# deserializer.net
KiCad netlist of a schematic drawn in Altium Designer
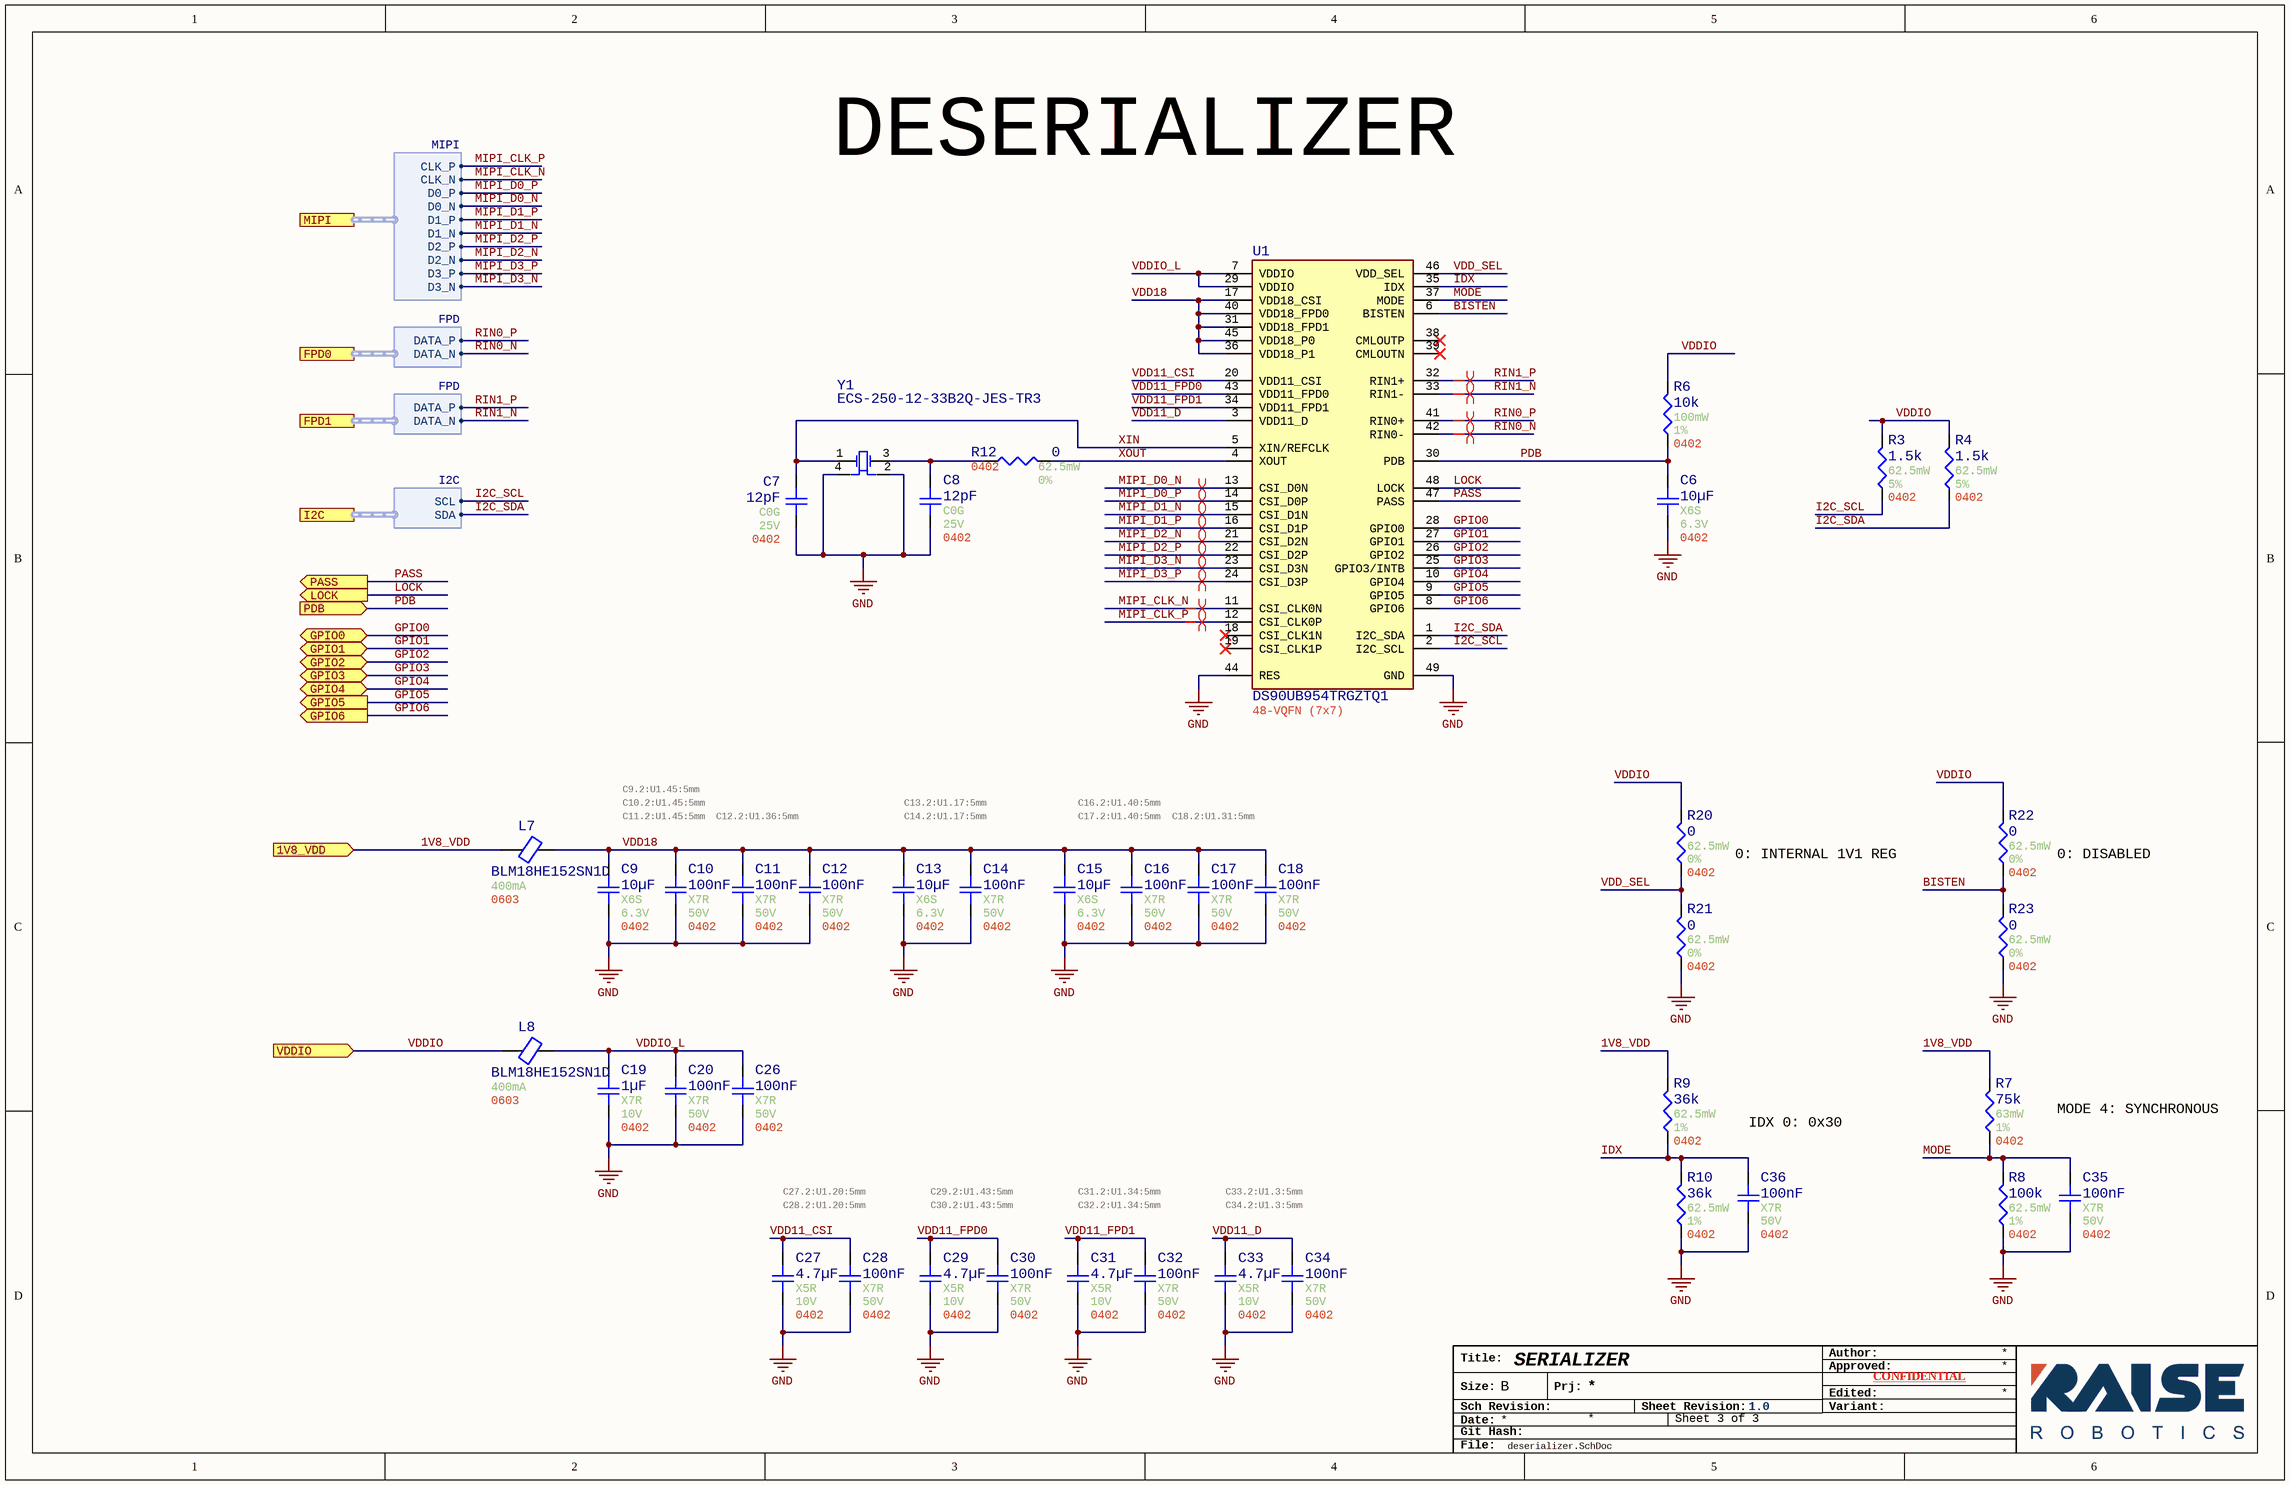
[diagram p0: deserializer.SchDoc]

(export (version "E")
  (design (tool "Eeschema 10.0.6"))
  (components
    (comp (ref "C6")
      (value "10µF")
      (footprint "Generic 0402 capacitor")
      (description "Multilayer Ceramic Capacitors MLCC - SMD/SMT 0402 10uF 6.3VDC 20% X6S AEC-Q200")
      (fields
        (field (name "TEMPERATURE COEFFICIENT") "X6S")
        (field (name "VOLTAGE RATING") "6.3V")
        (field (name "CASE/PACKAGE") "0402")
        (field (name "TOLERANCE") "20%")
        (field (name "Comment") "GRT155C80J106ME13J")
      )
      (libsource (lib "Raise Robotics") (part "Unpolarized Capacitor"))
    )
    (comp (ref "C7")
      (value "12pF")
      (footprint "Generic 0402 capacitor")
      (fields
        (field (name "TEMPERATURE COEFFICIENT") "C0G")
        (field (name "VOLTAGE RATING") "25V")
        (field (name "CASE/PACKAGE") "0402")
        (field (name "TOLERANCE") "5%")
        (field (name "Comment") "GRT1555C1E120JA02J")
      )
      (libsource (lib "Raise Robotics") (part "Unpolarized Capacitor"))
    )
    (comp (ref "C8")
      (value "12pF")
      (footprint "Generic 0402 capacitor")
      (fields
        (field (name "TEMPERATURE COEFFICIENT") "C0G")
        (field (name "VOLTAGE RATING") "25V")
        (field (name "CASE/PACKAGE") "0402")
        (field (name "TOLERANCE") "5%")
        (field (name "Comment") "GRT1555C1E120JA02J")
      )
      (libsource (lib "Raise Robotics") (part "Unpolarized Capacitor"))
    )
    (comp (ref "C9")
      (value "10µF")
      (footprint "Generic 0402 capacitor")
      (description "Multilayer Ceramic Capacitors MLCC - SMD/SMT 0402 10uF 6.3VDC 20% X6S AEC-Q200")
      (fields
        (field (name "TEMPERATURE COEFFICIENT") "X6S")
        (field (name "VOLTAGE RATING") "6.3V")
        (field (name "CASE/PACKAGE") "0402")
        (field (name "TOLERANCE") "20%")
        (field (name "PLACENEAR") "C9.2:U1.45:5mm")
        (field (name "Comment") "GRT155C80J106ME13J")
      )
      (libsource (lib "Raise Robotics") (part "Unpolarized Capacitor"))
    )
    (comp (ref "C10")
      (value "100nF")
      (footprint "Generic 0402 capacitor")
      (fields
        (field (name "TEMPERATURE COEFFICIENT") "X7R")
        (field (name "VOLTAGE RATING") "50V")
        (field (name "CASE/PACKAGE") "0402")
        (field (name "TOLERANCE") "10%")
        (field (name "PLACENEAR") "C10.2:U1.45:5mm")
        (field (name "Comment") "GRT155R71H104KE01D")
      )
      (libsource (lib "Raise Robotics") (part "Unpolarized Capacitor"))
    )
    (comp (ref "C11")
      (value "100nF")
      (footprint "Generic 0402 capacitor")
      (fields
        (field (name "TEMPERATURE COEFFICIENT") "X7R")
        (field (name "VOLTAGE RATING") "50V")
        (field (name "CASE/PACKAGE") "0402")
        (field (name "TOLERANCE") "10%")
        (field (name "PLACENEAR") "C11.2:U1.45:5mm")
        (field (name "Comment") "GRT155R71H104KE01D")
      )
      (libsource (lib "Raise Robotics") (part "Unpolarized Capacitor"))
    )
    (comp (ref "C12")
      (value "100nF")
      (footprint "Generic 0402 capacitor")
      (fields
        (field (name "TEMPERATURE COEFFICIENT") "X7R")
        (field (name "VOLTAGE RATING") "50V")
        (field (name "CASE/PACKAGE") "0402")
        (field (name "TOLERANCE") "10%")
        (field (name "PLACENEAR") "C12.2:U1.36:5mm")
        (field (name "Comment") "GRT155R71H104KE01D")
      )
      (libsource (lib "Raise Robotics") (part "Unpolarized Capacitor"))
    )
    (comp (ref "C13")
      (value "10µF")
      (footprint "Generic 0402 capacitor")
      (description "Multilayer Ceramic Capacitors MLCC - SMD/SMT 0402 10uF 6.3VDC 20% X6S AEC-Q200")
      (fields
        (field (name "TEMPERATURE COEFFICIENT") "X6S")
        (field (name "VOLTAGE RATING") "6.3V")
        (field (name "CASE/PACKAGE") "0402")
        (field (name "TOLERANCE") "20%")
        (field (name "PLACENEAR") "C13.2:U1.17:5mm")
        (field (name "Comment") "GRT155C80J106ME13J")
      )
      (libsource (lib "Raise Robotics") (part "Unpolarized Capacitor"))
    )
    (comp (ref "C14")
      (value "100nF")
      (footprint "Generic 0402 capacitor")
      (fields
        (field (name "TEMPERATURE COEFFICIENT") "X7R")
        (field (name "VOLTAGE RATING") "50V")
        (field (name "CASE/PACKAGE") "0402")
        (field (name "TOLERANCE") "10%")
        (field (name "PLACENEAR") "C14.2:U1.17:5mm")
        (field (name "Comment") "GRT155R71H104KE01D")
      )
      (libsource (lib "Raise Robotics") (part "Unpolarized Capacitor"))
    )
    (comp (ref "C15")
      (value "10µF")
      (footprint "Generic 0402 capacitor")
      (description "Multilayer Ceramic Capacitors MLCC - SMD/SMT 0402 10uF 6.3VDC 20% X6S AEC-Q200")
      (fields
        (field (name "TEMPERATURE COEFFICIENT") "X6S")
        (field (name "VOLTAGE RATING") "6.3V")
        (field (name "CASE/PACKAGE") "0402")
        (field (name "TOLERANCE") "20%")
        (field (name "Comment") "GRT155C80J106ME13J")
      )
      (libsource (lib "Raise Robotics") (part "Unpolarized Capacitor"))
    )
    (comp (ref "C16")
      (value "100nF")
      (footprint "Generic 0402 capacitor")
      (fields
        (field (name "TEMPERATURE COEFFICIENT") "X7R")
        (field (name "VOLTAGE RATING") "50V")
        (field (name "CASE/PACKAGE") "0402")
        (field (name "TOLERANCE") "10%")
        (field (name "PLACENEAR") "C16.2:U1.40:5mm")
        (field (name "Comment") "GRT155R71H104KE01D")
      )
      (libsource (lib "Raise Robotics") (part "Unpolarized Capacitor"))
    )
    (comp (ref "C17")
      (value "100nF")
      (footprint "Generic 0402 capacitor")
      (fields
        (field (name "TEMPERATURE COEFFICIENT") "X7R")
        (field (name "VOLTAGE RATING") "50V")
        (field (name "CASE/PACKAGE") "0402")
        (field (name "TOLERANCE") "10%")
        (field (name "PLACENEAR") "C17.2:U1.40:5mm")
        (field (name "Comment") "GRT155R71H104KE01D")
      )
      (libsource (lib "Raise Robotics") (part "Unpolarized Capacitor"))
    )
    (comp (ref "C18")
      (value "100nF")
      (footprint "Generic 0402 capacitor")
      (fields
        (field (name "TEMPERATURE COEFFICIENT") "X7R")
        (field (name "VOLTAGE RATING") "50V")
        (field (name "CASE/PACKAGE") "0402")
        (field (name "TOLERANCE") "10%")
        (field (name "PLACENEAR") "C18.2:U1.31:5mm")
        (field (name "Comment") "GRT155R71H104KE01D")
      )
      (libsource (lib "Raise Robotics") (part "Unpolarized Capacitor"))
    )
    (comp (ref "C19")
      (value "1µF")
      (footprint "Generic 0402 capacitor")
      (description "Cap Cer 1UF 20V X7T 0402")
      (fields
        (field (name "TEMPERATURE COEFFICIENT") "X7R")
        (field (name "VOLTAGE RATING") "10V")
        (field (name "CASE/PACKAGE") "0402")
        (field (name "TOLERANCE") "20%")
        (field (name "Comment") "MAASL105CD7105MFCA01")
      )
      (libsource (lib "Raise Robotics") (part "Unpolarized Capacitor"))
    )
    (comp (ref "C20")
      (value "100nF")
      (footprint "Generic 0402 capacitor")
      (fields
        (field (name "TEMPERATURE COEFFICIENT") "X7R")
        (field (name "VOLTAGE RATING") "50V")
        (field (name "CASE/PACKAGE") "0402")
        (field (name "TOLERANCE") "10%")
        (field (name "Comment") "GRT155R71H104KE01D")
      )
      (libsource (lib "Raise Robotics") (part "Unpolarized Capacitor"))
    )
    (comp (ref "C26")
      (value "100nF")
      (footprint "Generic 0402 capacitor")
      (fields
        (field (name "TEMPERATURE COEFFICIENT") "X7R")
        (field (name "VOLTAGE RATING") "50V")
        (field (name "CASE/PACKAGE") "0402")
        (field (name "TOLERANCE") "10%")
        (field (name "Comment") "GRT155R71H104KE01D")
      )
      (libsource (lib "Raise Robotics") (part "Unpolarized Capacitor"))
    )
    (comp (ref "C27")
      (value "4.7µF")
      (footprint "Generic 0402 capacitor")
      (fields
        (field (name "TEMPERATURE COEFFICIENT") "X5R")
        (field (name "VOLTAGE RATING") "10V")
        (field (name "CASE/PACKAGE") "0402")
        (field (name "TOLERANCE") "0%")
        (field (name "PLACENEAR") "C27.2:U1.20:5mm")
        (field (name "Comment") "GRT155R61A475ME13D")
      )
      (libsource (lib "Raise Robotics") (part "Unpolarized Capacitor"))
    )
    (comp (ref "C28")
      (value "100nF")
      (footprint "Generic 0402 capacitor")
      (fields
        (field (name "TEMPERATURE COEFFICIENT") "X7R")
        (field (name "VOLTAGE RATING") "50V")
        (field (name "CASE/PACKAGE") "0402")
        (field (name "TOLERANCE") "10%")
        (field (name "PLACENEAR") "C28.2:U1.20:5mm")
        (field (name "Comment") "GRT155R71H104KE01D")
      )
      (libsource (lib "Raise Robotics") (part "Unpolarized Capacitor"))
    )
    (comp (ref "C29")
      (value "4.7µF")
      (footprint "Generic 0402 capacitor")
      (fields
        (field (name "TEMPERATURE COEFFICIENT") "X5R")
        (field (name "VOLTAGE RATING") "10V")
        (field (name "CASE/PACKAGE") "0402")
        (field (name "TOLERANCE") "0%")
        (field (name "PLACENEAR") "C29.2:U1.43:5mm")
        (field (name "Comment") "GRT155R61A475ME13D")
      )
      (libsource (lib "Raise Robotics") (part "Unpolarized Capacitor"))
    )
    (comp (ref "C30")
      (value "100nF")
      (footprint "Generic 0402 capacitor")
      (fields
        (field (name "TEMPERATURE COEFFICIENT") "X7R")
        (field (name "VOLTAGE RATING") "50V")
        (field (name "CASE/PACKAGE") "0402")
        (field (name "TOLERANCE") "10%")
        (field (name "PLACENEAR") "C30.2:U1.43:5mm")
        (field (name "Comment") "GRT155R71H104KE01D")
      )
      (libsource (lib "Raise Robotics") (part "Unpolarized Capacitor"))
    )
    (comp (ref "C31")
      (value "4.7µF")
      (footprint "Generic 0402 capacitor")
      (fields
        (field (name "TEMPERATURE COEFFICIENT") "X5R")
        (field (name "VOLTAGE RATING") "10V")
        (field (name "CASE/PACKAGE") "0402")
        (field (name "TOLERANCE") "0%")
        (field (name "PLACENEAR") "C31.2:U1.34:5mm")
        (field (name "Comment") "GRT155R61A475ME13D")
      )
      (libsource (lib "Raise Robotics") (part "Unpolarized Capacitor"))
    )
    (comp (ref "C32")
      (value "100nF")
      (footprint "Generic 0402 capacitor")
      (fields
        (field (name "TEMPERATURE COEFFICIENT") "X7R")
        (field (name "VOLTAGE RATING") "50V")
        (field (name "CASE/PACKAGE") "0402")
        (field (name "TOLERANCE") "10%")
        (field (name "PLACENEAR") "C32.2:U1.34:5mm")
        (field (name "Comment") "GRT155R71H104KE01D")
      )
      (libsource (lib "Raise Robotics") (part "Unpolarized Capacitor"))
    )
    (comp (ref "C33")
      (value "4.7µF")
      (footprint "Generic 0402 capacitor")
      (fields
        (field (name "TEMPERATURE COEFFICIENT") "X5R")
        (field (name "VOLTAGE RATING") "10V")
        (field (name "CASE/PACKAGE") "0402")
        (field (name "TOLERANCE") "0%")
        (field (name "PLACENEAR") "C33.2:U1.3:5mm")
        (field (name "Comment") "GRT155R61A475ME13D")
      )
      (libsource (lib "Raise Robotics") (part "Unpolarized Capacitor"))
    )
    (comp (ref "C34")
      (value "100nF")
      (footprint "Generic 0402 capacitor")
      (fields
        (field (name "TEMPERATURE COEFFICIENT") "X7R")
        (field (name "VOLTAGE RATING") "50V")
        (field (name "CASE/PACKAGE") "0402")
        (field (name "TOLERANCE") "10%")
        (field (name "PLACENEAR") "C34.2:U1.3:5mm")
        (field (name "Comment") "GRT155R71H104KE01D")
      )
      (libsource (lib "Raise Robotics") (part "Unpolarized Capacitor"))
    )
    (comp (ref "C35")
      (value "100nF")
      (footprint "Generic 0402 capacitor")
      (fields
        (field (name "TEMPERATURE COEFFICIENT") "X7R")
        (field (name "VOLTAGE RATING") "50V")
        (field (name "CASE/PACKAGE") "0402")
        (field (name "TOLERANCE") "10%")
        (field (name "Comment") "GRT155R71H104KE01D")
      )
      (libsource (lib "Raise Robotics") (part "Unpolarized Capacitor"))
    )
    (comp (ref "C36")
      (value "100nF")
      (footprint "Generic 0402 capacitor")
      (fields
        (field (name "TEMPERATURE COEFFICIENT") "X7R")
        (field (name "VOLTAGE RATING") "50V")
        (field (name "CASE/PACKAGE") "0402")
        (field (name "TOLERANCE") "10%")
        (field (name "Comment") "GRT155R71H104KE01D")
      )
      (libsource (lib "Raise Robotics") (part "Unpolarized Capacitor"))
    )
    (comp (ref "L7")
      (value "BLM18HE152SN1D")
      (footprint "0603_1.6x0.8x0.8mm_IND")
      (description "Ferrite Beads Multi-Layer 1.5KOhm 25% 100MHz 500mA 500mOhm DCR 0603 T/R")
      (fields
        (field (name "CURRENT RATING") "400mA")
        (field (name "CASE/PACKAGE") "0603")
        (field (name "TOLERANCE") "25%")
      )
      (libsource (lib "Raise Robotics") (part "Generic 2 pin ferrite bead"))
    )
    (comp (ref "L8")
      (value "BLM18HE152SN1D")
      (footprint "0603_1.6x0.8x0.8mm_IND")
      (description "Ferrite Beads Multi-Layer 1.5KOhm 25% 100MHz 500mA 500mOhm DCR 0603 T/R")
      (fields
        (field (name "CURRENT RATING") "400mA")
        (field (name "CASE/PACKAGE") "0603")
        (field (name "TOLERANCE") "25%")
      )
      (libsource (lib "Raise Robotics") (part "Generic 2 pin ferrite bead"))
    )
    (comp (ref "R3")
      (value "1.5k")
      (footprint "Generic 0402 Resistor")
      (description "Res Thick Film 0402 1.5K Ohm 5% 0.063W ±100ppm/°C Molded SMD Paper T/R")
      (fields
        (field (name "POWER") "62.5mW")
        (field (name "TOLERANCE") "5%")
        (field (name "CASE/PACKAGE") "0402")
        (field (name "Comment") "RMCF0402JT1K50")
      )
      (libsource (lib "Raise Robotics") (part "Resistor"))
    )
    (comp (ref "R4")
      (value "1.5k")
      (footprint "Generic 0402 Resistor")
      (description "Res Thick Film 0402 1.5K Ohm 5% 0.063W ±100ppm/°C Molded SMD Paper T/R")
      (fields
        (field (name "POWER") "62.5mW")
        (field (name "TOLERANCE") "5%")
        (field (name "CASE/PACKAGE") "0402")
        (field (name "Comment") "RMCF0402JT1K50")
      )
      (libsource (lib "Raise Robotics") (part "Resistor"))
    )
    (comp (ref "R6")
      (value "10k")
      (footprint "Generic 0402 Resistor")
      (description "Fixed Resistor, Thin Film, 0.1W, 10000ohm, 50V, 1% +/-Tol, 100ppm/Cel, Surface Mount, 0402")
      (fields
        (field (name "POWER") "100mW")
        (field (name "TOLERANCE") "1%")
        (field (name "CASE/PACKAGE") "0402")
        (field (name "MANUFACTURER PART NUMBER") "Blank")
        (field (name "Comment") "RNCP0402FTD10K0")
      )
      (libsource (lib "Raise Robotics") (part "Resistor"))
    )
    (comp (ref "R7")
      (value "75k")
      (footprint "Generic 0402 Resistor")
      (description "Res Thick Film 0402 75K Ohm 1% 0.063W(1/16W) ±100ppm/C Pad SMD T/R")
      (fields
        (field (name "POWER") "63mW")
        (field (name "TOLERANCE") "1%")
        (field (name "CASE/PACKAGE") "0402")
        (field (name "Comment") "WR04X7502FTL")
      )
      (libsource (lib "Raise Robotics") (part "Resistor"))
    )
    (comp (ref "R8")
      (value "100k")
      (footprint "Generic 0402 Resistor")
      (fields
        (field (name "POWER") "62.5mW")
        (field (name "TOLERANCE") "1%")
        (field (name "CASE/PACKAGE") "0402")
        (field (name "MANUFACTURER PART NUMBER") "Blank")
        (field (name "Comment") "WR04X1003FTL")
      )
      (libsource (lib "Raise Robotics") (part "Resistor"))
    )
    (comp (ref "R9")
      (value "36k")
      (footprint "Generic 0402 Resistor")
      (fields
        (field (name "POWER") "62.5mW")
        (field (name "TOLERANCE") "1%")
        (field (name "CASE/PACKAGE") "0402")
        (field (name "Comment") "AC0402FR-0736KL")
      )
      (libsource (lib "Raise Robotics") (part "Resistor"))
    )
    (comp (ref "R10")
      (value "36k")
      (footprint "Generic 0402 Resistor")
      (fields
        (field (name "POWER") "62.5mW")
        (field (name "TOLERANCE") "1%")
        (field (name "CASE/PACKAGE") "0402")
        (field (name "Comment") "AC0402FR-0736KL")
      )
      (libsource (lib "Raise Robotics") (part "Resistor"))
    )
    (comp (ref "R12")
      (value "0")
      (footprint "Generic 0402 Resistor")
      (description "Fixed Resistor, Metal Glaze/thick Film, 0.0625W, 0ohm, Surface Mount, 0402")
      (fields
        (field (name "POWER") "62.5mW")
        (field (name "TOLERANCE") "0%")
        (field (name "CASE/PACKAGE") "0402")
        (field (name "MANUFACTURER PART NUMBER") "Blank")
        (field (name "Comment") "WR04X000PTL")
      )
      (libsource (lib "Raise Robotics") (part "Resistor"))
    )
    (comp (ref "R20")
      (value "0")
      (footprint "Generic 0402 Resistor")
      (description "Fixed Resistor, Metal Glaze/thick Film, 0.0625W, 0ohm, Surface Mount, 0402")
      (fields
        (field (name "POWER") "62.5mW")
        (field (name "TOLERANCE") "0%")
        (field (name "CASE/PACKAGE") "0402")
        (field (name "MANUFACTURER PART NUMBER") "Blank")
        (field (name "Comment") "WR04X000PTL")
      )
      (libsource (lib "Raise Robotics") (part "Resistor"))
    )
    (comp (ref "R21")
      (value "0")
      (footprint "Generic 0402 Resistor")
      (description "Fixed Resistor, Metal Glaze/thick Film, 0.0625W, 0ohm, Surface Mount, 0402")
      (fields
        (field (name "POWER") "62.5mW")
        (field (name "TOLERANCE") "0%")
        (field (name "CASE/PACKAGE") "0402")
        (field (name "MANUFACTURER PART NUMBER") "Blank")
        (field (name "Comment") "WR04X000PTL")
      )
      (libsource (lib "Raise Robotics") (part "Resistor"))
    )
    (comp (ref "R22")
      (value "0")
      (footprint "Generic 0402 Resistor")
      (description "Fixed Resistor, Metal Glaze/thick Film, 0.0625W, 0ohm, Surface Mount, 0402")
      (fields
        (field (name "POWER") "62.5mW")
        (field (name "TOLERANCE") "0%")
        (field (name "CASE/PACKAGE") "0402")
        (field (name "MANUFACTURER PART NUMBER") "Blank")
        (field (name "Comment") "WR04X000PTL")
      )
      (libsource (lib "Raise Robotics") (part "Resistor"))
    )
    (comp (ref "R23")
      (value "0")
      (footprint "Generic 0402 Resistor")
      (description "Fixed Resistor, Metal Glaze/thick Film, 0.0625W, 0ohm, Surface Mount, 0402")
      (fields
        (field (name "POWER") "62.5mW")
        (field (name "TOLERANCE") "0%")
        (field (name "CASE/PACKAGE") "0402")
        (field (name "MANUFACTURER PART NUMBER") "Blank")
        (field (name "Comment") "WR04X000PTL")
      )
      (libsource (lib "Raise Robotics") (part "Resistor"))
    )
    (comp (ref "U1")
      (value "DS90UB954TRGZTQ1")
      (footprint "VQFN-48_7x7x1.0mm_P0.5mm")
      (fields (field (name "CASE/PACKAGE") "48-VQFN (7x7)"))
      (libsource (lib "Raise Robotics") (part "DS90UB954TRGZTQ1"))
    )
    (comp (ref "Y1")
      (value "ECS-250-12-33B2Q-JES-TR3")
      (footprint "ECS-250-12-33B2Q-JES-TR3")
      (description "Crystal 25.000 Mhz 12PF SMD")
      (libsource (lib "Raise Robotics") (part "XTAL-2"))
    )
  )
  (nets
    (net (code "4") (name "/1V8_VDD") (class "Default")
      (node (ref "L7") (pin "1") (pinfunction "1_1") (pintype "passive"))
      (node (ref "R7") (pin "2") (pinfunction "2_2") (pintype "passive"))
      (node (ref "R9") (pin "2") (pinfunction "2_2") (pintype "passive"))
    )
    (net (code "5") (name "/BISTEN") (class "Default")
      (node (ref "R22") (pin "1") (pinfunction "1_1") (pintype "passive"))
      (node (ref "R23") (pin "2") (pinfunction "2_2") (pintype "passive"))
      (node (ref "U1") (pin "6") (pinfunction "BISTEN_6") (pintype "passive"))
    )
    (net (code "6") (name "/GPIO0") (class "Default")
      (node (ref "U1") (pin "28") (pinfunction "GPIO0_28") (pintype "passive"))
    )
    (net (code "7") (name "/GPIO1") (class "Default")
      (node (ref "U1") (pin "27") (pinfunction "GPIO1_27") (pintype "passive"))
    )
    (net (code "8") (name "/GPIO2") (class "Default")
      (node (ref "U1") (pin "26") (pinfunction "GPIO2_26") (pintype "passive"))
    )
    (net (code "9") (name "/GPIO3") (class "Default")
      (node (ref "U1") (pin "25") (pinfunction "GPIO3/INTB_25") (pintype "passive"))
    )
    (net (code "10") (name "/GPIO4") (class "Default")
      (node (ref "U1") (pin "10") (pinfunction "GPIO4_10") (pintype "passive"))
    )
    (net (code "11") (name "/GPIO5") (class "Default")
      (node (ref "U1") (pin "9") (pinfunction "GPIO5_9") (pintype "passive"))
    )
    (net (code "12") (name "/GPIO6") (class "Default")
      (node (ref "U1") (pin "8") (pinfunction "GPIO6_8") (pintype "passive"))
    )
    (net (code "13") (name "/I2C_SCL") (class "Default")
      (node (ref "R3") (pin "1") (pinfunction "1_1") (pintype "passive"))
      (node (ref "U1") (pin "2") (pinfunction "I2C_SCL_2") (pintype "passive"))
    )
    (net (code "14") (name "/I2C_SDA") (class "Default")
      (node (ref "R4") (pin "1") (pinfunction "1_1") (pintype "passive"))
      (node (ref "U1") (pin "1") (pinfunction "I2C_SDA_1") (pintype "passive"))
    )
    (net (code "15") (name "/IDX") (class "Default")
      (node (ref "C36") (pin "2") (pinfunction "2_2") (pintype "passive"))
      (node (ref "R10") (pin "2") (pinfunction "2_2") (pintype "passive"))
      (node (ref "R9") (pin "1") (pinfunction "1_1") (pintype "passive"))
      (node (ref "U1") (pin "35") (pinfunction "IDX_35") (pintype "passive"))
    )
    (net (code "16") (name "/LOCK") (class "Default")
      (node (ref "U1") (pin "48") (pinfunction "LOCK_48") (pintype "passive"))
    )
    (net (code "17") (name "/MIPI_CLK_N") (class "Default")
      (node (ref "U1") (pin "11") (pinfunction "CSI_CLK0N_11") (pintype "passive"))
    )
    (net (code "18") (name "/MIPI_CLK_P") (class "Default")
      (node (ref "U1") (pin "12") (pinfunction "CSI_CLK0P_12") (pintype "passive"))
    )
    (net (code "19") (name "/MIPI_D0_N") (class "Default")
      (node (ref "U1") (pin "13") (pinfunction "CSI_D0N_13") (pintype "passive"))
    )
    (net (code "20") (name "/MIPI_D0_P") (class "Default")
      (node (ref "U1") (pin "14") (pinfunction "CSI_D0P_14") (pintype "passive"))
    )
    (net (code "21") (name "/MIPI_D1_N") (class "Default")
      (node (ref "U1") (pin "15") (pinfunction "CSI_D1N_15") (pintype "passive"))
    )
    (net (code "22") (name "/MIPI_D1_P") (class "Default")
      (node (ref "U1") (pin "16") (pinfunction "CSI_D1P_16") (pintype "passive"))
    )
    (net (code "23") (name "/MIPI_D2_N") (class "Default")
      (node (ref "U1") (pin "21") (pinfunction "CSI_D2N_21") (pintype "passive"))
    )
    (net (code "24") (name "/MIPI_D2_P") (class "Default")
      (node (ref "U1") (pin "22") (pinfunction "CSI_D2P_22") (pintype "passive"))
    )
    (net (code "25") (name "/MIPI_D3_N") (class "Default")
      (node (ref "U1") (pin "23") (pinfunction "CSI_D3N_23") (pintype "passive"))
    )
    (net (code "26") (name "/MIPI_D3_P") (class "Default")
      (node (ref "U1") (pin "24") (pinfunction "CSI_D3P_24") (pintype "passive"))
    )
    (net (code "27") (name "/MODE") (class "Default")
      (node (ref "C35") (pin "2") (pinfunction "2_2") (pintype "passive"))
      (node (ref "R7") (pin "1") (pinfunction "1_1") (pintype "passive"))
      (node (ref "R8") (pin "2") (pinfunction "2_2") (pintype "passive"))
      (node (ref "U1") (pin "37") (pinfunction "MODE_37") (pintype "passive"))
    )
    (net (code "28") (name "/PASS") (class "Default")
      (node (ref "U1") (pin "47") (pinfunction "PASS_47") (pintype "passive"))
    )
    (net (code "29") (name "/PDB") (class "Default")
      (node (ref "C6") (pin "2") (pinfunction "2_2") (pintype "passive"))
      (node (ref "R6") (pin "1") (pinfunction "1_1") (pintype "passive"))
      (node (ref "U1") (pin "30") (pinfunction "PDB_30") (pintype "passive"))
    )
    (net (code "30") (name "/RIN0_N") (class "Default")
      (node (ref "U1") (pin "42") (pinfunction "RIN0-_42") (pintype "passive"))
    )
    (net (code "31") (name "/RIN0_P") (class "Default")
      (node (ref "U1") (pin "41") (pinfunction "RIN0+_41") (pintype "passive"))
    )
    (net (code "32") (name "/RIN1_N") (class "Default")
      (node (ref "U1") (pin "33") (pinfunction "RIN1-_33") (pintype "passive"))
    )
    (net (code "33") (name "/RIN1_P") (class "Default")
      (node (ref "U1") (pin "32") (pinfunction "RIN1+_32") (pintype "passive"))
    )
    (net (code "34") (name "/VDD11_CSI") (class "Default")
      (node (ref "C27") (pin "2") (pinfunction "2_2") (pintype "passive"))
      (node (ref "C28") (pin "2") (pinfunction "2_2") (pintype "passive"))
      (node (ref "U1") (pin "20") (pinfunction "VDD11_CSI_20") (pintype "passive"))
    )
    (net (code "35") (name "/VDD11_D") (class "Default")
      (node (ref "C33") (pin "2") (pinfunction "2_2") (pintype "passive"))
      (node (ref "C34") (pin "2") (pinfunction "2_2") (pintype "passive"))
      (node (ref "U1") (pin "3") (pinfunction "VDD11_D_3") (pintype "passive"))
    )
    (net (code "36") (name "/VDD11_FPD0") (class "Default")
      (node (ref "C29") (pin "2") (pinfunction "2_2") (pintype "passive"))
      (node (ref "C30") (pin "2") (pinfunction "2_2") (pintype "passive"))
      (node (ref "U1") (pin "43") (pinfunction "VDD11_FPD0_43") (pintype "passive"))
    )
    (net (code "37") (name "/VDD11_FPD1") (class "Default")
      (node (ref "C31") (pin "2") (pinfunction "2_2") (pintype "passive"))
      (node (ref "C32") (pin "2") (pinfunction "2_2") (pintype "passive"))
      (node (ref "U1") (pin "34") (pinfunction "VDD11_FPD1_34") (pintype "passive"))
    )
    (net (code "38") (name "/VDD18") (class "Default")
      (node (ref "C10") (pin "2") (pinfunction "2_2") (pintype "passive"))
      (node (ref "C11") (pin "2") (pinfunction "2_2") (pintype "passive"))
      (node (ref "C12") (pin "2") (pinfunction "2_2") (pintype "passive"))
      (node (ref "C13") (pin "2") (pinfunction "2_2") (pintype "passive"))
      (node (ref "C14") (pin "2") (pinfunction "2_2") (pintype "passive"))
      (node (ref "C15") (pin "2") (pinfunction "2_2") (pintype "passive"))
      (node (ref "C16") (pin "2") (pinfunction "2_2") (pintype "passive"))
      (node (ref "C17") (pin "2") (pinfunction "2_2") (pintype "passive"))
      (node (ref "C18") (pin "2") (pinfunction "2_2") (pintype "passive"))
      (node (ref "C9") (pin "2") (pinfunction "2_2") (pintype "passive"))
      (node (ref "L7") (pin "2") (pinfunction "2_2") (pintype "passive"))
      (node (ref "U1") (pin "17") (pinfunction "VDD18_CSI_17") (pintype "passive"))
      (node (ref "U1") (pin "31") (pinfunction "VDD18_FPD1_31") (pintype "passive"))
      (node (ref "U1") (pin "36") (pinfunction "VDD18_P1_36") (pintype "passive"))
      (node (ref "U1") (pin "40") (pinfunction "VDD18_FPD0_40") (pintype "passive"))
      (node (ref "U1") (pin "45") (pinfunction "VDD18_P0_45") (pintype "passive"))
    )
    (net (code "39") (name "/VDDIO") (class "Default")
      (node (ref "L8") (pin "1") (pinfunction "1_1") (pintype "passive"))
      (node (ref "R20") (pin "2") (pinfunction "2_2") (pintype "passive"))
      (node (ref "R22") (pin "2") (pinfunction "2_2") (pintype "passive"))
      (node (ref "R3") (pin "2") (pinfunction "2_2") (pintype "passive"))
      (node (ref "R4") (pin "2") (pinfunction "2_2") (pintype "passive"))
      (node (ref "R6") (pin "2") (pinfunction "2_2") (pintype "passive"))
    )
    (net (code "40") (name "/VDDIO_L") (class "Default")
      (node (ref "C19") (pin "2") (pinfunction "2_2") (pintype "passive"))
      (node (ref "C20") (pin "2") (pinfunction "2_2") (pintype "passive"))
      (node (ref "C26") (pin "2") (pinfunction "2_2") (pintype "passive"))
      (node (ref "L8") (pin "2") (pinfunction "2_2") (pintype "passive"))
      (node (ref "U1") (pin "29") (pinfunction "VDDIO_29") (pintype "passive"))
      (node (ref "U1") (pin "7") (pinfunction "VDDIO_7") (pintype "passive"))
    )
    (net (code "41") (name "/VDD_SEL") (class "Default")
      (node (ref "R20") (pin "1") (pinfunction "1_1") (pintype "passive"))
      (node (ref "R21") (pin "2") (pinfunction "2_2") (pintype "passive"))
      (node (ref "U1") (pin "46") (pinfunction "VDD_SEL_46") (pintype "passive"))
    )
    (net (code "42") (name "/XIN") (class "Default")
      (node (ref "C7") (pin "2") (pinfunction "2_2") (pintype "passive"))
      (node (ref "U1") (pin "5") (pinfunction "XIN/REFCLK_5") (pintype "passive"))
      (node (ref "Y1") (pin "1") (pinfunction "1_1") (pintype "passive"))
    )
    (net (code "43") (name "/XOUT") (class "Default")
      (node (ref "R12") (pin "2") (pinfunction "2_2") (pintype "passive"))
      (node (ref "U1") (pin "4") (pinfunction "XOUT_4") (pintype "passive"))
    )
    (net (code "47") (name "GND") (class "Default")
      (node (ref "C10") (pin "1") (pinfunction "1_1") (pintype "passive"))
      (node (ref "C11") (pin "1") (pinfunction "1_1") (pintype "passive"))
      (node (ref "C12") (pin "1") (pinfunction "1_1") (pintype "passive"))
      (node (ref "C13") (pin "1") (pinfunction "1_1") (pintype "passive"))
      (node (ref "C14") (pin "1") (pinfunction "1_1") (pintype "passive"))
      (node (ref "C15") (pin "1") (pinfunction "1_1") (pintype "passive"))
      (node (ref "C16") (pin "1") (pinfunction "1_1") (pintype "passive"))
      (node (ref "C17") (pin "1") (pinfunction "1_1") (pintype "passive"))
      (node (ref "C18") (pin "1") (pinfunction "1_1") (pintype "passive"))
      (node (ref "C19") (pin "1") (pinfunction "1_1") (pintype "passive"))
      (node (ref "C20") (pin "1") (pinfunction "1_1") (pintype "passive"))
      (node (ref "C26") (pin "1") (pinfunction "1_1") (pintype "passive"))
      (node (ref "C27") (pin "1") (pinfunction "1_1") (pintype "passive"))
      (node (ref "C28") (pin "1") (pinfunction "1_1") (pintype "passive"))
      (node (ref "C29") (pin "1") (pinfunction "1_1") (pintype "passive"))
      (node (ref "C30") (pin "1") (pinfunction "1_1") (pintype "passive"))
      (node (ref "C31") (pin "1") (pinfunction "1_1") (pintype "passive"))
      (node (ref "C32") (pin "1") (pinfunction "1_1") (pintype "passive"))
      (node (ref "C33") (pin "1") (pinfunction "1_1") (pintype "passive"))
      (node (ref "C34") (pin "1") (pinfunction "1_1") (pintype "passive"))
      (node (ref "C35") (pin "1") (pinfunction "1_1") (pintype "passive"))
      (node (ref "C36") (pin "1") (pinfunction "1_1") (pintype "passive"))
      (node (ref "C6") (pin "1") (pinfunction "1_1") (pintype "passive"))
      (node (ref "C7") (pin "1") (pinfunction "1_1") (pintype "passive"))
      (node (ref "C8") (pin "1") (pinfunction "1_1") (pintype "passive"))
      (node (ref "C9") (pin "1") (pinfunction "1_1") (pintype "passive"))
      (node (ref "R10") (pin "1") (pinfunction "1_1") (pintype "passive"))
      (node (ref "R21") (pin "1") (pinfunction "1_1") (pintype "passive"))
      (node (ref "R23") (pin "1") (pinfunction "1_1") (pintype "passive"))
      (node (ref "R8") (pin "1") (pinfunction "1_1") (pintype "passive"))
      (node (ref "U1") (pin "44") (pinfunction "RES_44") (pintype "passive"))
      (node (ref "U1") (pin "49") (pinfunction "GND_49") (pintype "passive"))
      (node (ref "Y1") (pin "2") (pinfunction "2_2") (pintype "passive"))
      (node (ref "Y1") (pin "4") (pinfunction "4_4") (pintype "passive"))
    )
    (net (code "48") (name "Net-(C8-Pad2)") (class "Default")
      (node (ref "C8") (pin "2") (pinfunction "2_2") (pintype "passive"))
      (node (ref "R12") (pin "1") (pinfunction "1_1") (pintype "passive"))
      (node (ref "Y1") (pin "3") (pinfunction "3_3") (pintype "passive"))
    )
    (net (code "49") (name "unconnected-(U1-CMLOUTN-Pad39)") (class "Default")
      (node (ref "U1") (pin "39") (pinfunction "CMLOUTN_39") (pintype "passive+no_connect"))
    )
    (net (code "50") (name "unconnected-(U1-CMLOUTP-Pad38)") (class "Default")
      (node (ref "U1") (pin "38") (pinfunction "CMLOUTP_38") (pintype "passive+no_connect"))
    )
    (net (code "51") (name "unconnected-(U1-CSI_CLK1N-Pad18)") (class "Default")
      (node (ref "U1") (pin "18") (pinfunction "CSI_CLK1N_18") (pintype "passive+no_connect"))
    )
    (net (code "52") (name "unconnected-(U1-CSI_CLK1P-Pad19)") (class "Default")
      (node (ref "U1") (pin "19") (pinfunction "CSI_CLK1P_19") (pintype "passive+no_connect"))
    )
  )
)
